# Sheet_A1.net
KiCad netlist of a schematic drawn in Altium Designer
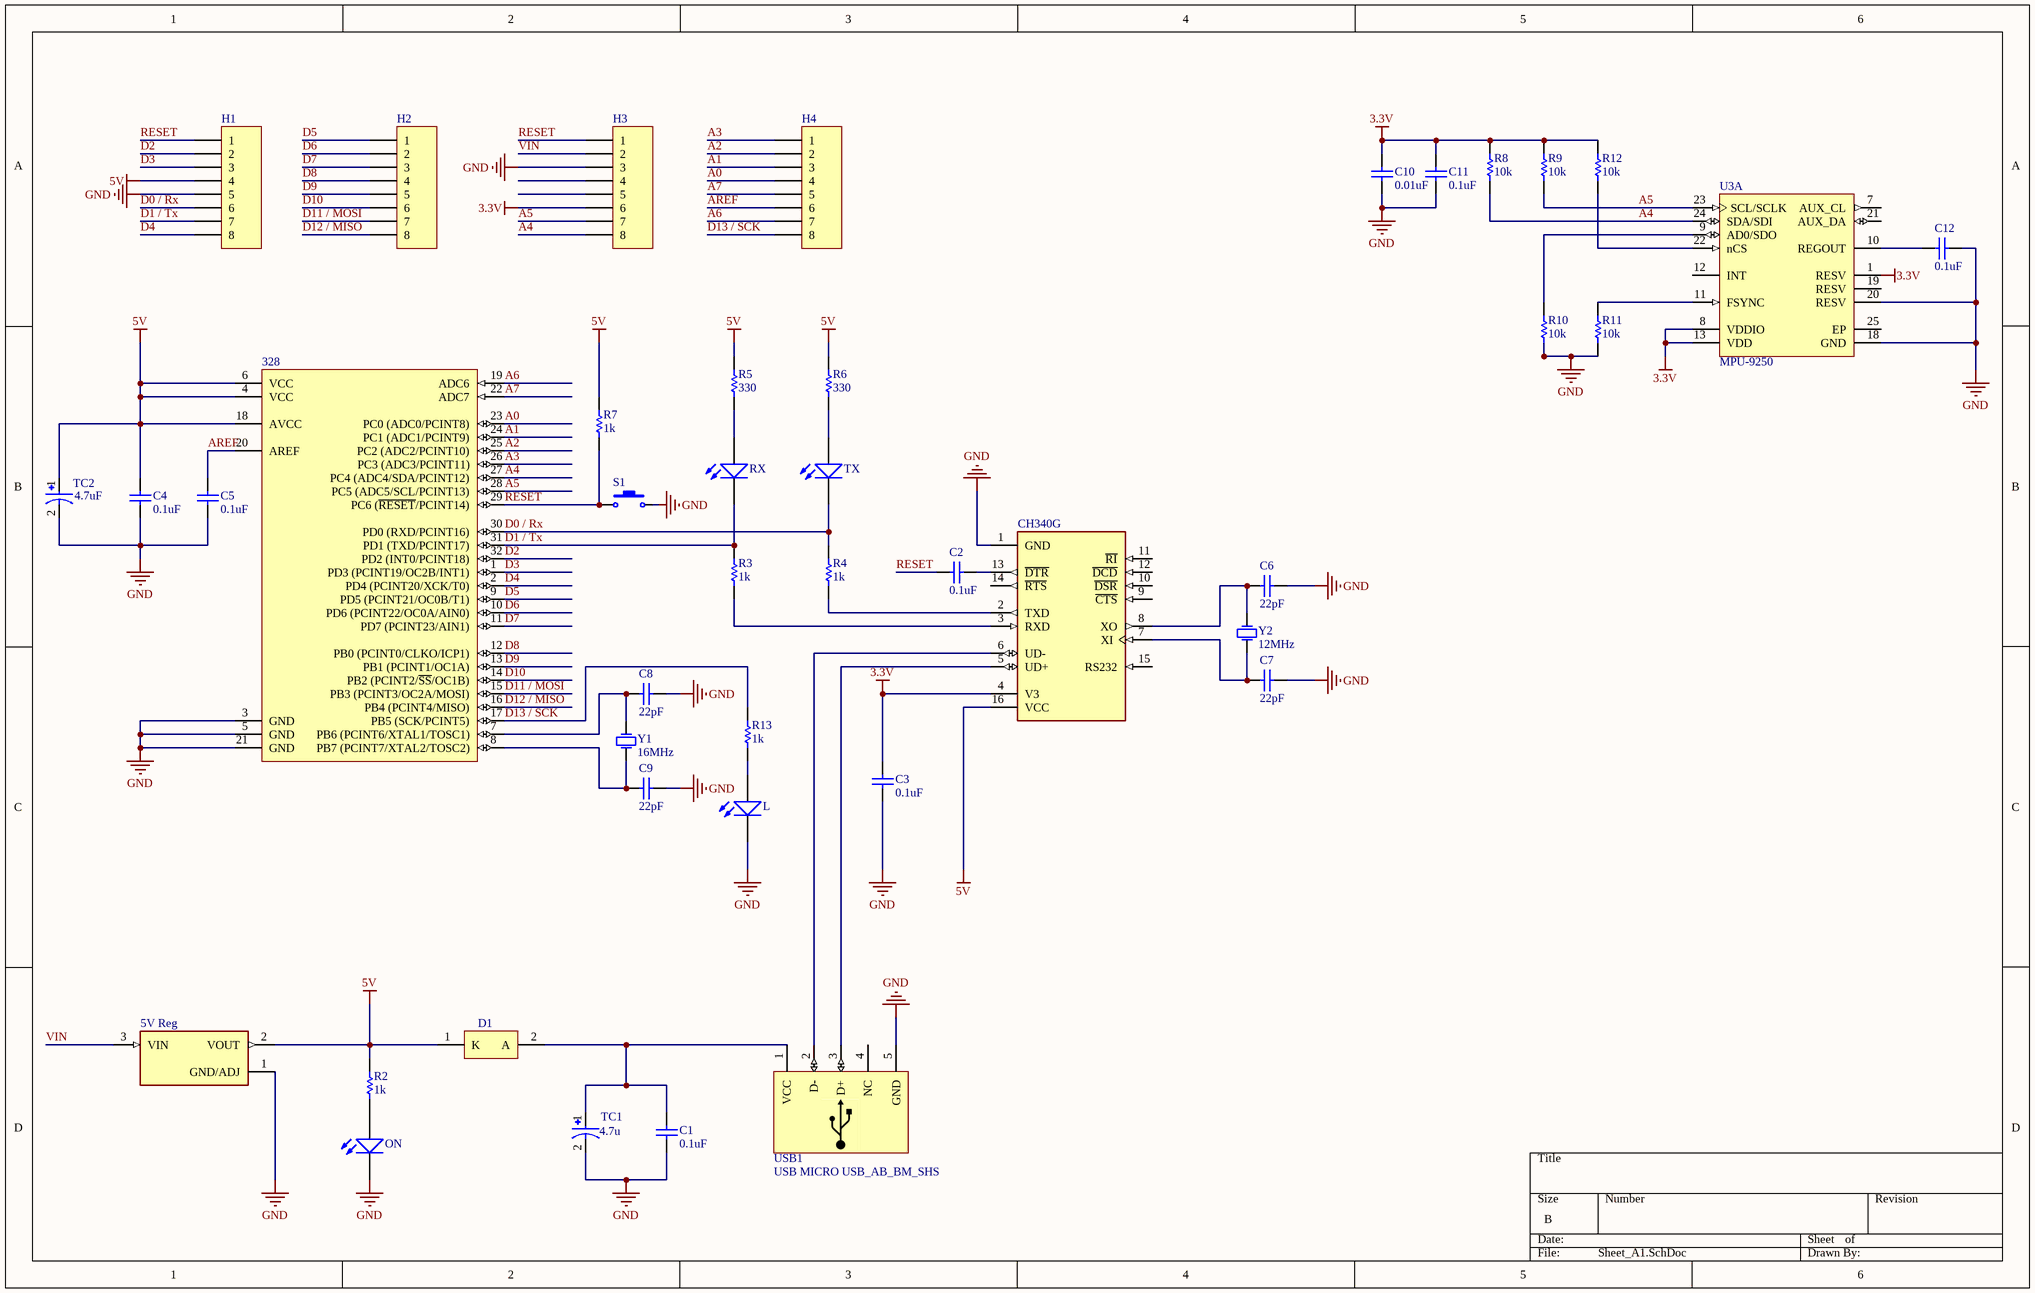
[diagram p0: Sheet_A1.SchDoc]

(export (version "E")
  (design (tool "Eeschema 10.0.6"))
  (components
    (comp (ref "5V Reg")
      (value "~")
      (footprint "SOT229P700X180-4N")
      (description "1A LOW DROPOUT VOLTAGE REGULATOR")
      (fields (field (name "MP") "AMS1117-5.0") (field (name "MF") "ams"))
      (libsource (lib "AMS1117-5.0") (part "AMS1117-5.0"))
    )
    (comp (ref "328")
      (value "~")
      (footprint "32A_L")
      (libsource (lib "Altium Content Vault") (part "MC-8B-ATM48-SQ32"))
    )
    (comp (ref "C1")
      (value "0.1uF")
      (footprint "CAP0805")
      (description "CAP0805")
      (libsource (lib "CAP0805") (part "CAP0805"))
    )
    (comp (ref "C2")
      (value "0.1uF")
      (footprint "CAP0805")
      (description "CAP0805")
      (libsource (lib "CAP0805") (part "CAP0805"))
    )
    (comp (ref "C3")
      (value "0.1uF")
      (footprint "CAP0805")
      (description "CAP0805")
      (libsource (lib "CAP0805") (part "CAP0805"))
    )
    (comp (ref "C4")
      (value "0.1uF")
      (footprint "CAP0805")
      (description "CAP0805")
      (libsource (lib "CAP0805") (part "CAP0805"))
    )
    (comp (ref "C5")
      (value "0.1uF")
      (footprint "CAP0805")
      (description "CAP0805")
      (libsource (lib "CAP0805") (part "CAP0805"))
    )
    (comp (ref "C6")
      (value "22pF")
      (footprint "CAP0805")
      (description "CAP0805")
      (libsource (lib "CAP0805") (part "CAP0805"))
    )
    (comp (ref "C7")
      (value "22pF")
      (footprint "CAP0805")
      (description "CAP0805")
      (libsource (lib "CAP0805") (part "CAP0805"))
    )
    (comp (ref "C8")
      (value "22pF")
      (footprint "CAP0805")
      (description "CAP0805")
      (libsource (lib "CAP0805") (part "CAP0805"))
    )
    (comp (ref "C9")
      (value "22pF")
      (footprint "CAP0805")
      (description "CAP0805")
      (libsource (lib "CAP0805") (part "CAP0805"))
    )
    (comp (ref "C10")
      (value "0.01uF")
      (footprint "CAP0805")
      (description "CAP0805")
      (libsource (lib "CAP0805") (part "CAP0805"))
    )
    (comp (ref "C11")
      (value "0.1uF")
      (footprint "CAP0805")
      (description "CAP0805")
      (libsource (lib "CAP0805") (part "CAP0805"))
    )
    (comp (ref "C12")
      (value "0.1uF")
      (footprint "CAP0805")
      (description "CAP0805")
      (libsource (lib "CAP0805") (part "CAP0805"))
    )
    (comp (ref "CH340G")
      (value "~")
      (footprint "SOIC127P600X180-16N")
      (description "USB Interface Integrated Circuit")
      (fields (field (name "MP") "Ch340G") (field (name "MF") "WCH"))
      (libsource (lib "CH340G") (part "CH340G"))
    )
    (comp (ref "D1")
      (value "~")
      (footprint "ONSC-SMB-2-403A-03_V")
      (description "Schottky Power Rectifier, 2-Pin SMB, Pb-Free, Tape and Reel")
      (fields (field (name "MANUFACTURER") "On Semiconductor") (field (name "PARTNUMBER") "SS24T3G"))
      (libsource (lib "Altium Content Vault") (part "ONSC-D-K1A2-2_A"))
    )
    (comp (ref "H1") (value "~") (footprint "Header 8") (libsource (lib "Header 8") (part "Header 8")))
    (comp (ref "H2") (value "~") (footprint "Header 8") (libsource (lib "Header 8") (part "Header 8")))
    (comp (ref "H3") (value "~") (footprint "Header 8") (libsource (lib "Header 8") (part "Header 8")))
    (comp (ref "H4") (value "~") (footprint "Header 8") (libsource (lib "Header 8") (part "Header 8")))
    (comp (ref "L")
      (value "~")
      (footprint "LED_SMD_0805")
      (libsource (lib "LED_SMD_0805") (part "LED_SMD_0805"))
    )
    (comp (ref "ON")
      (value "~")
      (footprint "LED_SMD_0805")
      (libsource (lib "LED_SMD_0805") (part "LED_SMD_0805"))
    )
    (comp (ref "R2")
      (value "1k")
      (footprint "RES0805")
      (description "RES0805")
      (libsource (lib "RES0805") (part "RES0805"))
    )
    (comp (ref "R3")
      (value "1k")
      (footprint "RES0805")
      (description "RES0805")
      (libsource (lib "RES0805") (part "RES0805"))
    )
    (comp (ref "R4")
      (value "1k")
      (footprint "RES0805")
      (description "RES0805")
      (libsource (lib "RES0805") (part "RES0805"))
    )
    (comp (ref "R5")
      (value "330")
      (footprint "RES0805")
      (description "RES0805")
      (libsource (lib "RES0805") (part "RES0805"))
    )
    (comp (ref "R6")
      (value "330")
      (footprint "RES0805")
      (description "RES0805")
      (libsource (lib "RES0805") (part "RES0805"))
    )
    (comp (ref "R7")
      (value "1k")
      (footprint "RES0805")
      (description "RES0805")
      (libsource (lib "RES0805") (part "RES0805"))
    )
    (comp (ref "R8")
      (value "10k")
      (footprint "RES0805")
      (description "RES0805")
      (libsource (lib "RES0805") (part "RES0805"))
    )
    (comp (ref "R9")
      (value "10k")
      (footprint "RES0805")
      (description "RES0805")
      (libsource (lib "RES0805") (part "RES0805"))
    )
    (comp (ref "R10")
      (value "10k")
      (footprint "RES0805")
      (description "RES0805")
      (libsource (lib "RES0805") (part "RES0805"))
    )
    (comp (ref "R11")
      (value "10k")
      (footprint "RES0805")
      (description "RES0805")
      (libsource (lib "RES0805") (part "RES0805"))
    )
    (comp (ref "R12")
      (value "10k")
      (footprint "RES0805")
      (description "RES0805")
      (libsource (lib "RES0805") (part "RES0805"))
    )
    (comp (ref "R13")
      (value "1k")
      (footprint "RES0805")
      (description "RES0805")
      (libsource (lib "RES0805") (part "RES0805"))
    )
    (comp (ref "RX")
      (value "~")
      (footprint "LED_SMD_0805")
      (libsource (lib "LED_SMD_0805") (part "LED_SMD_0805"))
    )
    (comp (ref "S1")
      (value "~")
      (footprint "Push Button Switch SMD")
      (libsource (lib "Push Button Switch SMD") (part "Push Button Switch SMD"))
    )
    (comp (ref "TC1")
      (value "4.7u")
      (footprint "CAPMP3516X190N")
      (description "4.7 ÂµF Molded Tantalum Capacitors 25 V 1411 (3528 Metric), 1210 1.5Ohm")
      (fields (field (name "MP") "TAJB475K025RNJ") (field (name "MF") "AVX"))
      (libsource (lib "TAJB475K025RNJ") (part "TAJB475K025RNJ"))
    )
    (comp (ref "TC2")
      (value "4.7uF")
      (footprint "CAPMP3516X190N")
      (description "4.7 ÂµF Molded Tantalum Capacitors 25 V 1411 (3528 Metric), 1210 1.5Ohm")
      (fields (field (name "MP") "TAJB475K025RNJ") (field (name "MF") "AVX"))
      (libsource (lib "TAJB475K025RNJ") (part "TAJB475K025RNJ"))
    )
    (comp (ref "TX")
      (value "~")
      (footprint "LED_SMD_0805")
      (libsource (lib "LED_SMD_0805") (part "LED_SMD_0805"))
    )
    (comp (ref "U3")
      (value "MPU-9250")
      (footprint "INSE-QFN-24-1700X1540TP_M")
      (description "9-axis MotionTracking device, 2.4 to 3,6 V, -40 to 85 degC, 24-Pin QFN, RoHS, Tape and Reel")
      (fields (field (name "MANUFACTURER") "InvenSense"))
      (libsource (lib "Altium Content Vault") (part "INSE-MPU-9250-QFN-24"))
    )
    (comp (ref "USB1")
      (value "USB MICRO USB_AB_BM_SHS")
      (footprint "USB MICRO USB_AB_BM_SHS")
      (libsource (lib "USB MICRO USB_AB_BM_SHS") (part "USB MICRO USB_AB_BM_SHS"))
    )
    (comp (ref "Y1")
      (value "16MHz")
      (footprint "Crystal SMD")
      (description "Crystal SMD")
      (libsource (lib "Crystal SMD") (part "Crystal SMD"))
    )
    (comp (ref "Y2")
      (value "12MHz")
      (footprint "Crystal SMD")
      (description "Crystal SMD")
      (libsource (lib "Crystal SMD") (part "Crystal SMD"))
    )
  )
  (nets
    (net (code "1") (name "/A0") (class "Default")
      (node (ref "328") (pin "23") (pinfunction "PC0_(ADC0/PCINT8)_23") (pintype "bidirectional"))
      (node (ref "H4") (pin "4") (pinfunction "4_4") (pintype "passive"))
    )
    (net (code "2") (name "/A1") (class "Default")
      (node (ref "328") (pin "24") (pinfunction "PC1_(ADC1/PCINT9)_24") (pintype "bidirectional"))
      (node (ref "H4") (pin "3") (pinfunction "3_3") (pintype "passive"))
    )
    (net (code "3") (name "/A2") (class "Default")
      (node (ref "328") (pin "25") (pinfunction "PC2_(ADC2/PCINT10)_25") (pintype "bidirectional"))
      (node (ref "H4") (pin "2") (pinfunction "2_2") (pintype "passive"))
    )
    (net (code "4") (name "/A3") (class "Default")
      (node (ref "328") (pin "26") (pinfunction "PC3_(ADC3/PCINT11)_26") (pintype "bidirectional"))
      (node (ref "H4") (pin "1") (pinfunction "1_1") (pintype "passive"))
    )
    (net (code "5") (name "/A4") (class "Default")
      (node (ref "328") (pin "27") (pinfunction "PC4_(ADC4/SDA/PCINT12)_27") (pintype "bidirectional"))
      (node (ref "H3") (pin "8") (pinfunction "8_8") (pintype "passive"))
      (node (ref "R8") (pin "1") (pinfunction "1_1") (pintype "passive"))
      (node (ref "U3") (pin "24") (pinfunction "SDA/SDI_24") (pintype "bidirectional"))
    )
    (net (code "6") (name "/A5") (class "Default")
      (node (ref "328") (pin "28") (pinfunction "PC5_(ADC5/SCL/PCINT13)_28") (pintype "bidirectional"))
      (node (ref "H3") (pin "7") (pinfunction "7_7") (pintype "passive"))
      (node (ref "R9") (pin "1") (pinfunction "1_1") (pintype "passive"))
      (node (ref "U3") (pin "23") (pinfunction "SCL/SCLK_23") (pintype "input"))
    )
    (net (code "7") (name "/A6") (class "Default")
      (node (ref "328") (pin "19") (pinfunction "ADC6_19") (pintype "input"))
      (node (ref "H4") (pin "7") (pinfunction "7_7") (pintype "passive"))
    )
    (net (code "8") (name "/A7") (class "Default")
      (node (ref "328") (pin "22") (pinfunction "ADC7_22") (pintype "input"))
      (node (ref "H4") (pin "5") (pinfunction "5_5") (pintype "passive"))
    )
    (net (code "9") (name "/AREF") (class "Default")
      (node (ref "328") (pin "20") (pinfunction "AREF_20") (pintype "passive"))
      (node (ref "C5") (pin "2") (pinfunction "2_2") (pintype "passive"))
      (node (ref "H4") (pin "6") (pinfunction "6_6") (pintype "passive"))
    )
    (net (code "10") (name "/D0 {slash} Rx") (class "Default")
      (node (ref "328") (pin "30") (pinfunction "PD0_(RXD/PCINT16)_30") (pintype "bidirectional"))
      (node (ref "H1") (pin "6") (pinfunction "6_6") (pintype "passive"))
      (node (ref "R4") (pin "2") (pinfunction "2_2") (pintype "passive"))
      (node (ref "TX") (pin "1") (pinfunction "K_1") (pintype "passive"))
    )
    (net (code "11") (name "/D1 {slash} Tx") (class "Default")
      (node (ref "328") (pin "31") (pinfunction "PD1_(TXD/PCINT17)_31") (pintype "bidirectional"))
      (node (ref "H1") (pin "7") (pinfunction "7_7") (pintype "passive"))
      (node (ref "R3") (pin "2") (pinfunction "2_2") (pintype "passive"))
      (node (ref "RX") (pin "1") (pinfunction "K_1") (pintype "passive"))
    )
    (net (code "12") (name "/D2") (class "Default")
      (node (ref "328") (pin "32") (pinfunction "PD2_(INT0/PCINT18)_32") (pintype "bidirectional"))
      (node (ref "H1") (pin "2") (pinfunction "2_2") (pintype "passive"))
    )
    (net (code "13") (name "/D3") (class "Default")
      (node (ref "328") (pin "1") (pinfunction "PD3_(PCINT19/OC2B/INT1)_1") (pintype "bidirectional"))
      (node (ref "H1") (pin "3") (pinfunction "3_3") (pintype "passive"))
    )
    (net (code "14") (name "/D4") (class "Default")
      (node (ref "328") (pin "2") (pinfunction "PD4_(PCINT20/XCK/T0)_2") (pintype "bidirectional"))
      (node (ref "H1") (pin "8") (pinfunction "8_8") (pintype "passive"))
    )
    (net (code "15") (name "/D5") (class "Default")
      (node (ref "328") (pin "9") (pinfunction "PD5_(PCINT21/OC0B/T1)_9") (pintype "bidirectional"))
      (node (ref "H2") (pin "1") (pinfunction "1_1") (pintype "passive"))
    )
    (net (code "16") (name "/D6") (class "Default")
      (node (ref "328") (pin "10") (pinfunction "PD6_(PCINT22/OC0A/AIN0)_10") (pintype "bidirectional"))
      (node (ref "H2") (pin "2") (pinfunction "2_2") (pintype "passive"))
    )
    (net (code "17") (name "/D7") (class "Default")
      (node (ref "328") (pin "11") (pinfunction "PD7_(PCINT23/AIN1)_11") (pintype "bidirectional"))
      (node (ref "H2") (pin "3") (pinfunction "3_3") (pintype "passive"))
    )
    (net (code "18") (name "/D8") (class "Default")
      (node (ref "328") (pin "12") (pinfunction "PB0_(PCINT0/CLKO/ICP1)_12") (pintype "bidirectional"))
      (node (ref "H2") (pin "4") (pinfunction "4_4") (pintype "passive"))
    )
    (net (code "19") (name "/D9") (class "Default")
      (node (ref "328") (pin "13") (pinfunction "PB1_(PCINT1/OC1A)_13") (pintype "bidirectional"))
      (node (ref "H2") (pin "5") (pinfunction "5_5") (pintype "passive"))
    )
    (net (code "20") (name "/D10") (class "Default")
      (node (ref "328") (pin "14") (pinfunction "PB2_(PCINT2/~{SS}/OC1B)_14") (pintype "bidirectional"))
      (node (ref "H2") (pin "6") (pinfunction "6_6") (pintype "passive"))
    )
    (net (code "21") (name "/D11 {slash} MOSI") (class "Default")
      (node (ref "328") (pin "15") (pinfunction "PB3_(PCINT3/OC2A/MOSI)_15") (pintype "bidirectional"))
      (node (ref "H2") (pin "7") (pinfunction "7_7") (pintype "passive"))
    )
    (net (code "22") (name "/D12 {slash} MISO") (class "Default")
      (node (ref "328") (pin "16") (pinfunction "PB4_(PCINT4/MISO)_16") (pintype "bidirectional"))
      (node (ref "H2") (pin "8") (pinfunction "8_8") (pintype "passive"))
    )
    (net (code "23") (name "/D13 {slash} SCK") (class "Default")
      (node (ref "328") (pin "17") (pinfunction "PB5_(SCK/PCINT5)_17") (pintype "bidirectional"))
      (node (ref "H4") (pin "8") (pinfunction "8_8") (pintype "passive"))
      (node (ref "R13") (pin "1") (pinfunction "1_1") (pintype "passive"))
    )
    (net (code "24") (name "/RESET") (class "Default")
      (node (ref "328") (pin "29") (pinfunction "PC6_(~{RESET}/PCINT14)_29") (pintype "bidirectional"))
      (node (ref "C2") (pin "2") (pinfunction "2_2") (pintype "passive"))
      (node (ref "H1") (pin "1") (pinfunction "1_1") (pintype "passive"))
      (node (ref "H3") (pin "1") (pinfunction "1_1") (pintype "passive"))
      (node (ref "R7") (pin "1") (pinfunction "1_1") (pintype "passive"))
      (node (ref "S1") (pin "1") (pinfunction "1_1") (pintype "passive"))
    )
    (net (code "25") (name "/VIN") (class "Default")
      (node (ref "5V Reg") (pin "3") (pinfunction "VIN_3") (pintype "input"))
      (node (ref "H3") (pin "2") (pinfunction "2_2") (pintype "passive"))
    )
    (net (code "26") (name "3.3V") (class "Default")
      (node (ref "C10") (pin "2") (pinfunction "2_2") (pintype "passive"))
      (node (ref "C11") (pin "2") (pinfunction "2_2") (pintype "passive"))
      (node (ref "C3") (pin "2") (pinfunction "2_2") (pintype "passive"))
      (node (ref "CH340G") (pin "4") (pinfunction "V3_4") (pintype "power_in"))
      (node (ref "H3") (pin "6") (pinfunction "6_6") (pintype "passive"))
      (node (ref "R12") (pin "2") (pinfunction "2_2") (pintype "passive"))
      (node (ref "R8") (pin "2") (pinfunction "2_2") (pintype "passive"))
      (node (ref "R9") (pin "2") (pinfunction "2_2") (pintype "passive"))
      (node (ref "U3") (pin "1") (pinfunction "RESV_1") (pintype "power_in"))
      (node (ref "U3") (pin "13") (pinfunction "VDD_13") (pintype "power_in"))
      (node (ref "U3") (pin "8") (pinfunction "VDDIO_8") (pintype "power_in"))
    )
    (net (code "27") (name "5V") (class "Default")
      (node (ref "328") (pin "18") (pinfunction "AVCC_18") (pintype "power_in"))
      (node (ref "328") (pin "4") (pinfunction "VCC_4") (pintype "power_in"))
      (node (ref "328") (pin "6") (pinfunction "VCC_6") (pintype "power_in"))
      (node (ref "5V Reg") (pin "2") (pinfunction "VOUT_2") (pintype "output"))
      (node (ref "C4") (pin "1") (pinfunction "1_1") (pintype "passive"))
      (node (ref "CH340G") (pin "16") (pinfunction "VCC_16") (pintype "power_in"))
      (node (ref "D1") (pin "1") (pinfunction "K_1") (pintype "passive"))
      (node (ref "H1") (pin "4") (pinfunction "4_4") (pintype "passive"))
      (node (ref "R2") (pin "2") (pinfunction "2_2") (pintype "passive"))
      (node (ref "R5") (pin "2") (pinfunction "2_2") (pintype "passive"))
      (node (ref "R6") (pin "2") (pinfunction "2_2") (pintype "passive"))
      (node (ref "R7") (pin "2") (pinfunction "2_2") (pintype "passive"))
      (node (ref "TC2") (pin "1") (pinfunction "1_1") (pintype "passive"))
    )
    (net (code "28") (name "GND") (class "Default")
      (node (ref "328") (pin "21") (pinfunction "GND_21") (pintype "power_in"))
      (node (ref "328") (pin "3") (pinfunction "GND_3") (pintype "power_in"))
      (node (ref "328") (pin "5") (pinfunction "GND_5") (pintype "power_in"))
      (node (ref "5V Reg") (pin "1") (pinfunction "GND/ADJ_1") (pintype "power_in"))
      (node (ref "C1") (pin "1") (pinfunction "1_1") (pintype "passive"))
      (node (ref "C10") (pin "1") (pinfunction "1_1") (pintype "passive"))
      (node (ref "C11") (pin "1") (pinfunction "1_1") (pintype "passive"))
      (node (ref "C12") (pin "2") (pinfunction "2_2") (pintype "passive"))
      (node (ref "C3") (pin "1") (pinfunction "1_1") (pintype "passive"))
      (node (ref "C4") (pin "2") (pinfunction "2_2") (pintype "passive"))
      (node (ref "C5") (pin "1") (pinfunction "1_1") (pintype "passive"))
      (node (ref "C6") (pin "1") (pinfunction "1_1") (pintype "passive"))
      (node (ref "C7") (pin "1") (pinfunction "1_1") (pintype "passive"))
      (node (ref "C8") (pin "1") (pinfunction "1_1") (pintype "passive"))
      (node (ref "C9") (pin "1") (pinfunction "1_1") (pintype "passive"))
      (node (ref "CH340G") (pin "1") (pinfunction "GND_1") (pintype "power_in"))
      (node (ref "H1") (pin "5") (pinfunction "5_5") (pintype "passive"))
      (node (ref "H3") (pin "3") (pinfunction "3_3") (pintype "passive"))
      (node (ref "L") (pin "1") (pinfunction "K_1") (pintype "passive"))
      (node (ref "ON") (pin "1") (pinfunction "K_1") (pintype "passive"))
      (node (ref "R10") (pin "2") (pinfunction "2_2") (pintype "passive"))
      (node (ref "R11") (pin "1") (pinfunction "1_1") (pintype "passive"))
      (node (ref "S1") (pin "2") (pinfunction "2_2") (pintype "passive"))
      (node (ref "TC1") (pin "2") (pinfunction "2_2") (pintype "passive"))
      (node (ref "TC2") (pin "2") (pinfunction "2_2") (pintype "passive"))
      (node (ref "U3") (pin "18") (pinfunction "GND_18") (pintype "power_in"))
      (node (ref "U3") (pin "20") (pinfunction "RESV_20") (pintype "power_in"))
      (node (ref "USB1") (pin "5") (pinfunction "GND_5") (pintype "power_in"))
    )
    (net (code "29") (name "Net-(328-PB6_(PCINT6{slash}XTAL1{slash}TOSC1))") (class "Default")
      (node (ref "328") (pin "7") (pinfunction "PB6_(PCINT6/XTAL1/TOSC1)_7") (pintype "bidirectional"))
      (node (ref "C8") (pin "2") (pinfunction "2_2") (pintype "passive"))
      (node (ref "Y1") (pin "2") (pinfunction "OSC2_2") (pintype "passive"))
    )
    (net (code "30") (name "Net-(328-PB7_(PCINT7{slash}XTAL2{slash}TOSC2))") (class "Default")
      (node (ref "328") (pin "8") (pinfunction "PB7_(PCINT7/XTAL2/TOSC2)_8") (pintype "bidirectional"))
      (node (ref "C9") (pin "2") (pinfunction "2_2") (pintype "passive"))
      (node (ref "Y1") (pin "1") (pinfunction "OSC1_1") (pintype "passive"))
    )
    (net (code "31") (name "Net-(CH340G-RXD)") (class "Default")
      (node (ref "CH340G") (pin "3") (pinfunction "RXD_3") (pintype "input"))
      (node (ref "R3") (pin "1") (pinfunction "1_1") (pintype "passive"))
    )
    (net (code "32") (name "Net-(CH340G-TXD)") (class "Default")
      (node (ref "CH340G") (pin "2") (pinfunction "TXD_2") (pintype "output"))
      (node (ref "R4") (pin "1") (pinfunction "1_1") (pintype "passive"))
    )
    (net (code "33") (name "Net-(CH340G-UD+)") (class "Default")
      (node (ref "CH340G") (pin "5") (pinfunction "UD+_5") (pintype "bidirectional"))
      (node (ref "USB1") (pin "3") (pinfunction "D+_3") (pintype "bidirectional"))
    )
    (net (code "34") (name "Net-(CH340G-UD-)") (class "Default")
      (node (ref "CH340G") (pin "6") (pinfunction "UD-_6") (pintype "bidirectional"))
      (node (ref "USB1") (pin "2") (pinfunction "D-_2") (pintype "bidirectional"))
    )
    (net (code "35") (name "Net-(CH340G-XI)") (class "Default")
      (node (ref "C7") (pin "2") (pinfunction "2_2") (pintype "passive"))
      (node (ref "CH340G") (pin "7") (pinfunction "XI_7") (pintype "input"))
      (node (ref "Y2") (pin "1") (pinfunction "OSC1_1") (pintype "passive"))
    )
    (net (code "36") (name "Net-(CH340G-XO)") (class "Default")
      (node (ref "C6") (pin "2") (pinfunction "2_2") (pintype "passive"))
      (node (ref "CH340G") (pin "8") (pinfunction "XO_8") (pintype "output"))
      (node (ref "Y2") (pin "2") (pinfunction "OSC2_2") (pintype "passive"))
    )
    (net (code "37") (name "Net-(CH340G-~{DTR})") (class "Default")
      (node (ref "C2") (pin "1") (pinfunction "1_1") (pintype "passive"))
      (node (ref "CH340G") (pin "13") (pinfunction "~{DTR}_13") (pintype "output"))
    )
    (net (code "38") (name "Net-(D1-A)") (class "Default")
      (node (ref "C1") (pin "2") (pinfunction "2_2") (pintype "passive"))
      (node (ref "D1") (pin "2") (pinfunction "A_2") (pintype "passive"))
      (node (ref "TC1") (pin "1") (pinfunction "1_1") (pintype "passive"))
      (node (ref "USB1") (pin "1") (pinfunction "VCC_1") (pintype "power_in"))
    )
    (net (code "39") (name "Net-(L-A)") (class "Default")
      (node (ref "L") (pin "2") (pinfunction "A_2") (pintype "passive"))
      (node (ref "R13") (pin "2") (pinfunction "2_2") (pintype "passive"))
    )
    (net (code "40") (name "Net-(ON-A)") (class "Default")
      (node (ref "ON") (pin "2") (pinfunction "A_2") (pintype "passive"))
      (node (ref "R2") (pin "1") (pinfunction "1_1") (pintype "passive"))
    )
    (net (code "41") (name "Net-(RX-A)") (class "Default")
      (node (ref "R5") (pin "1") (pinfunction "1_1") (pintype "passive"))
      (node (ref "RX") (pin "2") (pinfunction "A_2") (pintype "passive"))
    )
    (net (code "42") (name "Net-(TX-A)") (class "Default")
      (node (ref "R6") (pin "1") (pinfunction "1_1") (pintype "passive"))
      (node (ref "TX") (pin "2") (pinfunction "A_2") (pintype "passive"))
    )
    (net (code "43") (name "Net-(U3A-AD0{slash}SDO)") (class "Default")
      (node (ref "R10") (pin "1") (pinfunction "1_1") (pintype "passive"))
      (node (ref "U3") (pin "9") (pinfunction "AD0/SDO_9") (pintype "bidirectional"))
    )
    (net (code "44") (name "Net-(U3A-FSYNC)") (class "Default")
      (node (ref "R11") (pin "2") (pinfunction "2_2") (pintype "passive"))
      (node (ref "U3") (pin "11") (pinfunction "FSYNC_11") (pintype "input"))
    )
    (net (code "45") (name "Net-(U3A-REGOUT)") (class "Default")
      (node (ref "C12") (pin "1") (pinfunction "1_1") (pintype "passive"))
      (node (ref "U3") (pin "10") (pinfunction "REGOUT_10") (pintype "passive"))
    )
    (net (code "46") (name "Net-(U3A-nCS)") (class "Default")
      (node (ref "R12") (pin "1") (pinfunction "1_1") (pintype "passive"))
      (node (ref "U3") (pin "22") (pinfunction "nCS_22") (pintype "input"))
    )
    (net (code "47") (name "unconnected-(CH340G-RS232-Pad15)") (class "Default")
      (node (ref "CH340G") (pin "15") (pinfunction "RS232_15") (pintype "input"))
    )
    (net (code "48") (name "unconnected-(CH340G-~{CTS}-Pad9)") (class "Default")
      (node (ref "CH340G") (pin "9") (pinfunction "~{CTS}_9") (pintype "input"))
    )
    (net (code "49") (name "unconnected-(CH340G-~{DCD}-Pad12)") (class "Default")
      (node (ref "CH340G") (pin "12") (pinfunction "~{DCD}_12") (pintype "input"))
    )
    (net (code "50") (name "unconnected-(CH340G-~{DSR}-Pad10)") (class "Default")
      (node (ref "CH340G") (pin "10") (pinfunction "~{DSR}_10") (pintype "input"))
    )
    (net (code "51") (name "unconnected-(CH340G-~{RI}-Pad11)") (class "Default")
      (node (ref "CH340G") (pin "11") (pinfunction "~{RI}_11") (pintype "input"))
    )
    (net (code "52") (name "unconnected-(CH340G-~{RTS}-Pad14)") (class "Default")
      (node (ref "CH340G") (pin "14") (pinfunction "~{RTS}_14") (pintype "output"))
    )
    (net (code "53") (name "unconnected-(H3-Pad4)") (class "Default")
      (node (ref "H3") (pin "4") (pinfunction "4_4") (pintype "passive"))
    )
    (net (code "54") (name "unconnected-(H3-Pad5)") (class "Default")
      (node (ref "H3") (pin "5") (pinfunction "5_5") (pintype "passive"))
    )
    (net (code "55") (name "unconnected-(U3A-AUX_CL-Pad7)") (class "Default")
      (node (ref "U3") (pin "7") (pinfunction "AUX_CL_7") (pintype "output"))
    )
    (net (code "56") (name "unconnected-(U3A-AUX_DA-Pad21)") (class "Default")
      (node (ref "U3") (pin "21") (pinfunction "AUX_DA_21") (pintype "bidirectional"))
    )
    (net (code "57") (name "unconnected-(U3A-EP-Pad25)") (class "Default")
      (node (ref "U3") (pin "25") (pinfunction "EP_25") (pintype "passive"))
    )
    (net (code "58") (name "unconnected-(U3A-INT-Pad12)") (class "Default")
      (node (ref "U3") (pin "12") (pinfunction "INT_12") (pintype "tri_state"))
    )
    (net (code "59") (name "unconnected-(U3A-RESV-Pad19)") (class "Default")
      (node (ref "U3") (pin "19") (pinfunction "RESV_19") (pintype "passive"))
    )
    (net (code "60") (name "unconnected-(USB1-NC-Pad4)") (class "Default")
      (node (ref "USB1") (pin "4") (pinfunction "NC_4") (pintype "passive"))
    )
  )
)
